# 9235HallEffectV1_1.net
KiCad netlist of a schematic drawn in EAGLE
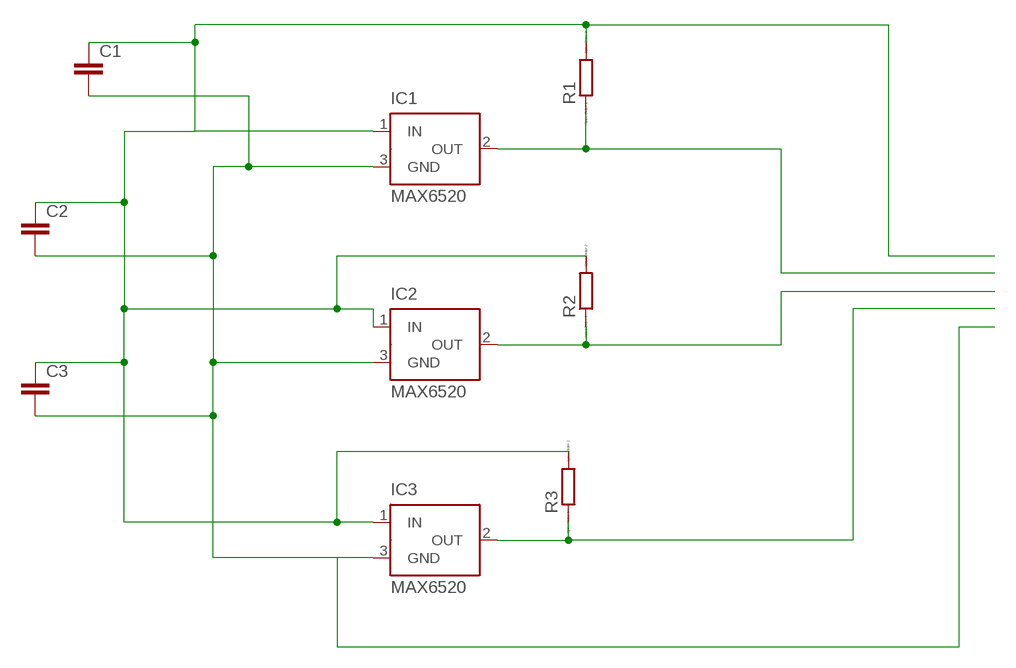
[diagram p0: schematic, sheet 1]

(export (version "E")
  (design (tool "Eeschema 10.0.6"))
  (components
    (comp (ref "C1")
      (value "C-EUC0603")
      (footprint "eagle-import:C0603")
      (libsource (lib "eagle-import") (part "C-EUC0603"))
    )
    (comp (ref "C2")
      (value "C-EUC0603")
      (footprint "eagle-import:C0603")
      (libsource (lib "eagle-import") (part "C-EUC0603"))
    )
    (comp (ref "C3")
      (value "C-EUC0603")
      (footprint "eagle-import:C0603")
      (libsource (lib "eagle-import") (part "C-EUC0603"))
    )
    (comp (ref "IC1")
      (value "MAX6520")
      (footprint "eagle-import:SOT23")
      (fields (field (name "MF") "MAXIM") (field (name "MPN") "MAX6520EUR-T"))
      (libsource (lib "eagle-import") (part "MAX6520"))
    )
    (comp (ref "IC2")
      (value "MAX6520")
      (footprint "eagle-import:SOT23")
      (fields (field (name "MF") "MAXIM") (field (name "MPN") "MAX6520EUR-T"))
      (libsource (lib "eagle-import") (part "MAX6520"))
    )
    (comp (ref "IC3")
      (value "MAX6520")
      (footprint "eagle-import:SOT23")
      (fields (field (name "MF") "MAXIM") (field (name "MPN") "MAX6520EUR-T"))
      (libsource (lib "eagle-import") (part "MAX6520"))
    )
    (comp (ref "R1")
      (value "RR0603")
      (footprint "eagle-import:R0603")
      (libsource (lib "eagle-import") (part "RR0603"))
    )
    (comp (ref "R2")
      (value "RR0603")
      (footprint "eagle-import:R0603")
      (libsource (lib "eagle-import") (part "RR0603"))
    )
    (comp (ref "R3")
      (value "RR0603")
      (footprint "eagle-import:R0603")
      (libsource (lib "eagle-import") (part "RR0603"))
    )
  )
  (nets
    (net (code "1") (name "Net-(IC1-GND)") (class "Default")
      (node (ref "C1") (pin "2") (pinfunction "2_2") (pintype "passive"))
      (node (ref "C2") (pin "2") (pinfunction "2_2") (pintype "passive"))
      (node (ref "C3") (pin "2") (pinfunction "2_2") (pintype "passive"))
      (node (ref "IC1") (pin "3") (pinfunction "GND_3") (pintype "power_in"))
      (node (ref "IC2") (pin "3") (pinfunction "GND_3") (pintype "power_in"))
      (node (ref "IC3") (pin "3") (pinfunction "GND_3") (pintype "power_in"))
    )
    (net (code "2") (name "Net-(IC1-IN)") (class "Default")
      (node (ref "C1") (pin "1") (pinfunction "1_1") (pintype "passive"))
      (node (ref "C2") (pin "1") (pinfunction "1_1") (pintype "passive"))
      (node (ref "C3") (pin "1") (pinfunction "1_1") (pintype "passive"))
      (node (ref "IC1") (pin "1") (pinfunction "IN_1") (pintype "input"))
      (node (ref "IC2") (pin "1") (pinfunction "IN_1") (pintype "input"))
      (node (ref "IC3") (pin "1") (pinfunction "IN_1") (pintype "input"))
      (node (ref "R1") (pin "2") (pinfunction "2_2") (pintype "passive"))
      (node (ref "R2") (pin "2") (pinfunction "2_2") (pintype "passive"))
      (node (ref "R3") (pin "2") (pinfunction "2_2") (pintype "passive"))
    )
    (net (code "3") (name "Net-(IC1-OUT)") (class "Default")
      (node (ref "IC1") (pin "2") (pinfunction "OUT_2") (pintype "output"))
      (node (ref "R1") (pin "1") (pinfunction "1_1") (pintype "passive"))
    )
    (net (code "4") (name "Net-(IC2-OUT)") (class "Default")
      (node (ref "IC2") (pin "2") (pinfunction "OUT_2") (pintype "output"))
      (node (ref "R2") (pin "1") (pinfunction "1_1") (pintype "passive"))
    )
    (net (code "5") (name "Net-(IC3-OUT)") (class "Default")
      (node (ref "IC3") (pin "2") (pinfunction "OUT_2") (pintype "output"))
      (node (ref "R3") (pin "1") (pinfunction "1_1") (pintype "passive"))
    )
  )
)
